# optoshield-low1.net
KiCad netlist of a schematic drawn in EAGLE
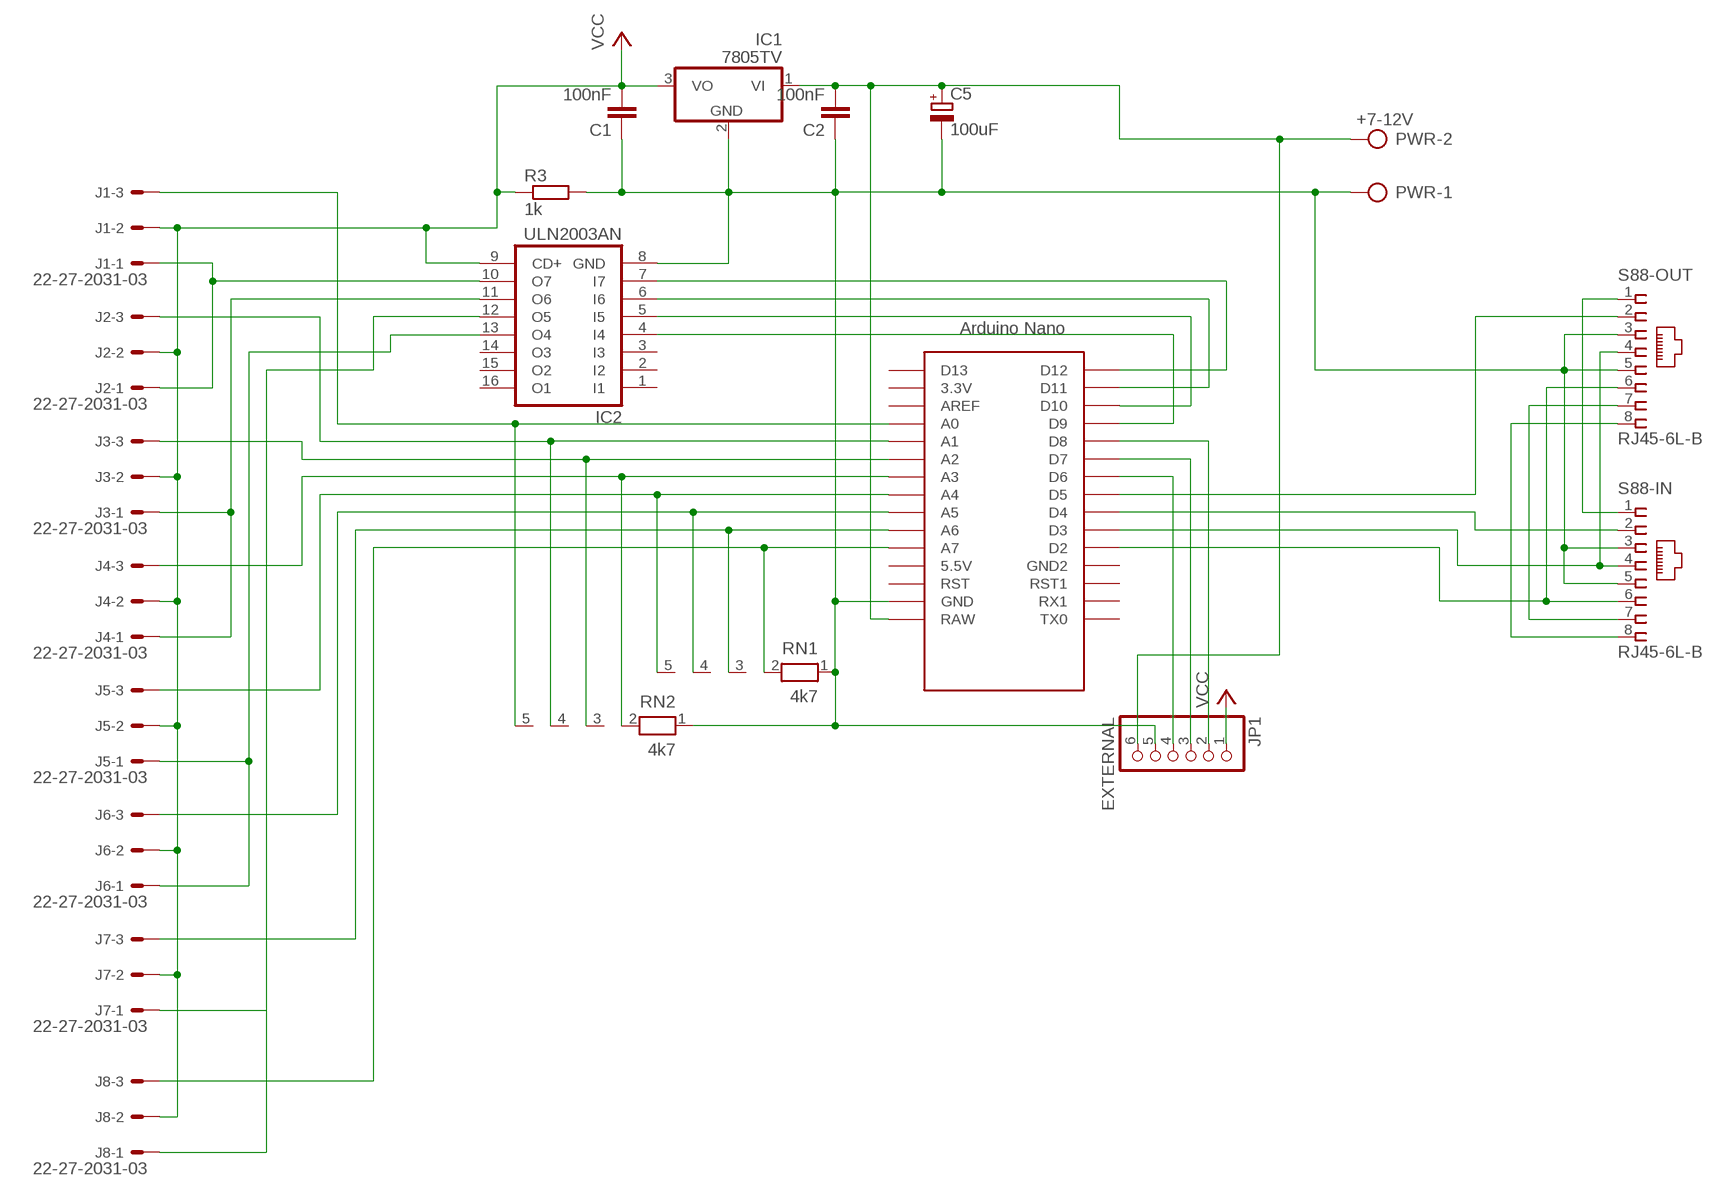
[diagram p0: schematic, sheet 1]

(export (version "E")
  (design (tool "Eeschema 10.0.6"))
  (components
    (comp (ref "C1")
      (value "100nF")
      (footprint "eagle-import:C025-025X050")
      (libsource (lib "eagle-import") (part "C-EU025-025X050"))
    )
    (comp (ref "C2")
      (value "100nF")
      (footprint "eagle-import:C025-025X050")
      (libsource (lib "eagle-import") (part "C-EU025-025X050"))
    )
    (comp (ref "C5")
      (value "100uF")
      (footprint "eagle-import:E3,5-10")
      (libsource (lib "eagle-import") (part "CPOL-EUE3.5-10"))
    )
    (comp (ref "IC1")
      (value "7805TV")
      (footprint "eagle-import:TO220V")
      (libsource (lib "eagle-import") (part "78TV05"))
    )
    (comp (ref "IC2")
      (value "ULN2003AN")
      (footprint "eagle-import:DIL16")
      (libsource (lib "eagle-import") (part "ULN2003AN"))
    )
    (comp (ref "J1")
      (value "22-27-2031-03")
      (footprint "eagle-import:6410-03")
      (libsource (lib "eagle-import") (part "22-?-0327-2031"))
    )
    (comp (ref "J2")
      (value "22-27-2031-03")
      (footprint "eagle-import:6410-03")
      (libsource (lib "eagle-import") (part "22-?-0327-2031"))
    )
    (comp (ref "J3")
      (value "22-27-2031-03")
      (footprint "eagle-import:6410-03")
      (libsource (lib "eagle-import") (part "22-?-0327-2031"))
    )
    (comp (ref "J4")
      (value "22-27-2031-03")
      (footprint "eagle-import:6410-03")
      (libsource (lib "eagle-import") (part "22-?-0327-2031"))
    )
    (comp (ref "J5")
      (value "22-27-2031-03")
      (footprint "eagle-import:6410-03")
      (libsource (lib "eagle-import") (part "22-?-0327-2031"))
    )
    (comp (ref "J6")
      (value "22-27-2031-03")
      (footprint "eagle-import:6410-03")
      (libsource (lib "eagle-import") (part "22-?-0327-2031"))
    )
    (comp (ref "J7")
      (value "22-27-2031-03")
      (footprint "eagle-import:6410-03")
      (libsource (lib "eagle-import") (part "22-?-0327-2031"))
    )
    (comp (ref "J8")
      (value "22-27-2031-03")
      (footprint "eagle-import:6410-03")
      (libsource (lib "eagle-import") (part "22-?-0327-2031"))
    )
    (comp (ref "JP1")
      (value "EXTERNAL")
      (footprint "eagle-import:1X06")
      (libsource (lib "eagle-import") (part "PINHD-1X6"))
    )
    (comp (ref "PWR")
      (value "+7-12V")
      (footprint "eagle-import:AK500_2")
      (libsource (lib "eagle-import") (part "AK500/2"))
    )
    (comp (ref "R3")
      (value "1k")
      (footprint "eagle-import:0207_10")
      (libsource (lib "eagle-import") (part "R-EU_0207/10"))
    )
    (comp (ref "RN1")
      (value "4k7")
      (footprint "eagle-import:RN-5")
      (libsource (lib "eagle-import") (part "RN04"))
    )
    (comp (ref "RN2")
      (value "4k7")
      (footprint "eagle-import:RN-5")
      (libsource (lib "eagle-import") (part "RN04"))
    )
    (comp (ref "S88-IN")
      (value "RJ45-6L-B")
      (footprint "eagle-import:RJ45-NO-SHIELD")
      (libsource (lib "eagle-import") (part "RJ45-6L-B"))
    )
    (comp (ref "S88-OUT")
      (value "RJ45-6L-B")
      (footprint "eagle-import:RJ45-NO-SHIELD")
      (libsource (lib "eagle-import") (part "RJ45-6L-B"))
    )
    (comp (ref "U$1")
      (value "NANO")
      (footprint "eagle-import:NANO")
      (libsource (lib "eagle-import") (part "NANO"))
    )
  )
  (nets
    (net (code "1") (name "Net-(IC1-GND)") (class "Default")
      (node (ref "C1") (pin "1") (pinfunction "1_1") (pintype "passive"))
      (node (ref "C2") (pin "1") (pinfunction "1_1") (pintype "passive"))
      (node (ref "C5") (pin "-") (pinfunction "-_-") (pintype "passive"))
      (node (ref "IC1") (pin "2") (pinfunction "GND_2") (pintype "passive"))
      (node (ref "IC2") (pin "8") (pinfunction "GND_8") (pintype "power_in"))
      (node (ref "JP1") (pin "5") (pinfunction "5_5") (pintype "passive"))
      (node (ref "PWR") (pin "1") (pinfunction "KL_1") (pintype "passive"))
      (node (ref "R3") (pin "2") (pinfunction "2_2") (pintype "passive"))
      (node (ref "RN1") (pin "1") (pinfunction "1_1") (pintype "passive"))
      (node (ref "RN2") (pin "1") (pinfunction "1_1") (pintype "passive"))
      (node (ref "S88-IN") (pin "3") (pinfunction "3_3") (pintype "passive"))
      (node (ref "S88-IN") (pin "5") (pinfunction "5_5") (pintype "passive"))
      (node (ref "S88-OUT") (pin "3") (pinfunction "3_3") (pintype "passive"))
      (node (ref "S88-OUT") (pin "5") (pinfunction "5_5") (pintype "passive"))
      (node (ref "U$1") (pin "GND") (pinfunction "GND_GND") (pintype "bidirectional"))
    )
    (net (code "2") (name "Net-(IC1-VI)") (class "Default")
      (node (ref "C2") (pin "2") (pinfunction "2_2") (pintype "passive"))
      (node (ref "C5") (pin "+") (pinfunction "+_+") (pintype "passive"))
      (node (ref "IC1") (pin "1") (pinfunction "VI_1") (pintype "input"))
      (node (ref "JP1") (pin "6") (pinfunction "6_6") (pintype "passive"))
      (node (ref "PWR") (pin "2") (pinfunction "KL_2") (pintype "passive"))
      (node (ref "U$1") (pin "RAW") (pinfunction "RAW_RAW") (pintype "bidirectional"))
    )
    (net (code "3") (name "Net-(IC2-I4)") (class "Default")
      (node (ref "IC2") (pin "4") (pinfunction "I4_4") (pintype "input"))
      (node (ref "U$1") (pin "D9") (pinfunction "D9_D9") (pintype "bidirectional"))
    )
    (net (code "4") (name "Net-(IC2-I5)") (class "Default")
      (node (ref "IC2") (pin "5") (pinfunction "I5_5") (pintype "input"))
      (node (ref "U$1") (pin "D10") (pinfunction "D10_D10") (pintype "bidirectional"))
    )
    (net (code "5") (name "Net-(IC2-I6)") (class "Default")
      (node (ref "IC2") (pin "6") (pinfunction "I6_6") (pintype "input"))
      (node (ref "U$1") (pin "D11") (pinfunction "D11_D11") (pintype "bidirectional"))
    )
    (net (code "6") (name "Net-(IC2-I7)") (class "Default")
      (node (ref "IC2") (pin "7") (pinfunction "I7_7") (pintype "input"))
      (node (ref "U$1") (pin "D12") (pinfunction "D12_D12") (pintype "bidirectional"))
    )
    (net (code "7") (name "Net-(IC2-O4)") (class "Default")
      (node (ref "IC2") (pin "13") (pinfunction "O4_13") (pintype "open_collector"))
      (node (ref "J5") (pin "1") (pinfunction "S_1") (pintype "passive"))
      (node (ref "J6") (pin "1") (pinfunction "S_1") (pintype "passive"))
    )
    (net (code "8") (name "Net-(IC2-O5)") (class "Default")
      (node (ref "IC2") (pin "12") (pinfunction "O5_12") (pintype "open_collector"))
      (node (ref "J7") (pin "1") (pinfunction "S_1") (pintype "passive"))
      (node (ref "J8") (pin "1") (pinfunction "S_1") (pintype "passive"))
    )
    (net (code "9") (name "Net-(IC2-O6)") (class "Default")
      (node (ref "IC2") (pin "11") (pinfunction "O6_11") (pintype "open_collector"))
      (node (ref "J3") (pin "1") (pinfunction "S_1") (pintype "passive"))
      (node (ref "J4") (pin "1") (pinfunction "S_1") (pintype "passive"))
    )
    (net (code "10") (name "Net-(IC2-O7)") (class "Default")
      (node (ref "IC2") (pin "10") (pinfunction "O7_10") (pintype "open_collector"))
      (node (ref "J1") (pin "1") (pinfunction "S_1") (pintype "passive"))
      (node (ref "J2") (pin "1") (pinfunction "S_1") (pintype "passive"))
    )
    (net (code "11") (name "Net-(J1C-S)") (class "Default")
      (node (ref "J1") (pin "3") (pinfunction "S_3") (pintype "passive"))
      (node (ref "RN2") (pin "5") (pinfunction "5_5") (pintype "passive"))
      (node (ref "U$1") (pin "A0") (pinfunction "A0_A0") (pintype "bidirectional"))
    )
    (net (code "12") (name "Net-(J2C-S)") (class "Default")
      (node (ref "J2") (pin "3") (pinfunction "S_3") (pintype "passive"))
      (node (ref "RN2") (pin "4") (pinfunction "4_4") (pintype "passive"))
      (node (ref "U$1") (pin "A1") (pinfunction "A1_A1") (pintype "bidirectional"))
    )
    (net (code "13") (name "Net-(J3C-S)") (class "Default")
      (node (ref "J3") (pin "3") (pinfunction "S_3") (pintype "passive"))
      (node (ref "RN2") (pin "3") (pinfunction "3_3") (pintype "passive"))
      (node (ref "U$1") (pin "A2") (pinfunction "A2_A2") (pintype "bidirectional"))
    )
    (net (code "14") (name "Net-(J4C-S)") (class "Default")
      (node (ref "J4") (pin "3") (pinfunction "S_3") (pintype "passive"))
      (node (ref "RN2") (pin "2") (pinfunction "2_2") (pintype "passive"))
      (node (ref "U$1") (pin "A3") (pinfunction "A3_A3") (pintype "bidirectional"))
    )
    (net (code "15") (name "Net-(J5C-S)") (class "Default")
      (node (ref "J5") (pin "3") (pinfunction "S_3") (pintype "passive"))
      (node (ref "RN1") (pin "5") (pinfunction "5_5") (pintype "passive"))
      (node (ref "U$1") (pin "A4") (pinfunction "A4_A4") (pintype "bidirectional"))
    )
    (net (code "16") (name "Net-(J6C-S)") (class "Default")
      (node (ref "J6") (pin "3") (pinfunction "S_3") (pintype "passive"))
      (node (ref "RN1") (pin "4") (pinfunction "4_4") (pintype "passive"))
      (node (ref "U$1") (pin "A5") (pinfunction "A5_A5") (pintype "bidirectional"))
    )
    (net (code "17") (name "Net-(J7C-S)") (class "Default")
      (node (ref "J7") (pin "3") (pinfunction "S_3") (pintype "passive"))
      (node (ref "RN1") (pin "3") (pinfunction "3_3") (pintype "passive"))
      (node (ref "U$1") (pin "A6") (pinfunction "A6_A6") (pintype "bidirectional"))
    )
    (net (code "18") (name "Net-(J8C-S)") (class "Default")
      (node (ref "J8") (pin "3") (pinfunction "S_3") (pintype "passive"))
      (node (ref "RN1") (pin "2") (pinfunction "2_2") (pintype "passive"))
      (node (ref "U$1") (pin "A7") (pinfunction "A7_A7") (pintype "bidirectional"))
    )
    (net (code "19") (name "Net-(JP1-Pad2)") (class "Default")
      (node (ref "JP1") (pin "2") (pinfunction "2_2") (pintype "passive"))
      (node (ref "U$1") (pin "D8") (pinfunction "D8_D8") (pintype "bidirectional"))
    )
    (net (code "20") (name "Net-(JP1-Pad3)") (class "Default")
      (node (ref "JP1") (pin "3") (pinfunction "3_3") (pintype "passive"))
      (node (ref "U$1") (pin "D7") (pinfunction "D7_D7") (pintype "bidirectional"))
    )
    (net (code "21") (name "Net-(JP1-Pad4)") (class "Default")
      (node (ref "JP1") (pin "4") (pinfunction "4_4") (pintype "passive"))
      (node (ref "U$1") (pin "D6") (pinfunction "D6_D6") (pintype "bidirectional"))
    )
    (net (code "22") (name "Net-(S88-IN-Pad1)") (class "Default")
      (node (ref "S88-IN") (pin "1") (pinfunction "1_1") (pintype "passive"))
      (node (ref "S88-OUT") (pin "1") (pinfunction "1_1") (pintype "passive"))
    )
    (net (code "23") (name "Net-(S88-IN-Pad2)") (class "Default")
      (node (ref "S88-IN") (pin "2") (pinfunction "2_2") (pintype "passive"))
      (node (ref "U$1") (pin "D4") (pinfunction "D4_D4") (pintype "bidirectional"))
    )
    (net (code "24") (name "Net-(S88-IN-Pad4)") (class "Default")
      (node (ref "S88-IN") (pin "4") (pinfunction "4_4") (pintype "passive"))
      (node (ref "S88-OUT") (pin "4") (pinfunction "4_4") (pintype "passive"))
      (node (ref "U$1") (pin "D3") (pinfunction "D3_D3") (pintype "bidirectional"))
    )
    (net (code "25") (name "Net-(S88-IN-Pad6)") (class "Default")
      (node (ref "S88-IN") (pin "6") (pinfunction "6_6") (pintype "passive"))
      (node (ref "S88-OUT") (pin "6") (pinfunction "6_6") (pintype "passive"))
      (node (ref "U$1") (pin "D2") (pinfunction "D2_D2") (pintype "bidirectional"))
    )
    (net (code "26") (name "Net-(S88-IN-Pad7)") (class "Default")
      (node (ref "S88-IN") (pin "7") (pinfunction "7_7") (pintype "passive"))
      (node (ref "S88-OUT") (pin "7") (pinfunction "7_7") (pintype "passive"))
    )
    (net (code "27") (name "Net-(S88-IN-Pad8)") (class "Default")
      (node (ref "S88-IN") (pin "8") (pinfunction "8_8") (pintype "passive"))
      (node (ref "S88-OUT") (pin "8") (pinfunction "8_8") (pintype "passive"))
    )
    (net (code "28") (name "Net-(S88-OUT-Pad2)") (class "Default")
      (node (ref "S88-OUT") (pin "2") (pinfunction "2_2") (pintype "passive"))
      (node (ref "U$1") (pin "D5") (pinfunction "D5_D5") (pintype "bidirectional"))
    )
    (net (code "29") (name "VCC") (class "Default")
      (node (ref "C1") (pin "2") (pinfunction "2_2") (pintype "passive"))
      (node (ref "IC1") (pin "3") (pinfunction "VO_3") (pintype "passive"))
      (node (ref "IC2") (pin "9") (pinfunction "CD+_9") (pintype "passive"))
      (node (ref "J1") (pin "2") (pinfunction "S_2") (pintype "passive"))
      (node (ref "J2") (pin "2") (pinfunction "S_2") (pintype "passive"))
      (node (ref "J3") (pin "2") (pinfunction "S_2") (pintype "passive"))
      (node (ref "J4") (pin "2") (pinfunction "S_2") (pintype "passive"))
      (node (ref "J5") (pin "2") (pinfunction "S_2") (pintype "passive"))
      (node (ref "J6") (pin "2") (pinfunction "S_2") (pintype "passive"))
      (node (ref "J7") (pin "2") (pinfunction "S_2") (pintype "passive"))
      (node (ref "J8") (pin "2") (pinfunction "S_2") (pintype "passive"))
      (node (ref "JP1") (pin "1") (pinfunction "1_1") (pintype "passive"))
      (node (ref "R3") (pin "1") (pinfunction "1_1") (pintype "passive"))
    )
    (net (code "30") (name "unconnected-(IC2-I1-Pad1)") (class "Default")
      (node (ref "IC2") (pin "1") (pinfunction "I1_1") (pintype "input"))
    )
    (net (code "31") (name "unconnected-(IC2-I2-Pad2)") (class "Default")
      (node (ref "IC2") (pin "2") (pinfunction "I2_2") (pintype "input"))
    )
    (net (code "32") (name "unconnected-(IC2-I3-Pad3)") (class "Default")
      (node (ref "IC2") (pin "3") (pinfunction "I3_3") (pintype "input"))
    )
    (net (code "33") (name "unconnected-(IC2-O1-Pad16)") (class "Default")
      (node (ref "IC2") (pin "16") (pinfunction "O1_16") (pintype "open_collector"))
    )
    (net (code "34") (name "unconnected-(IC2-O2-Pad15)") (class "Default")
      (node (ref "IC2") (pin "15") (pinfunction "O2_15") (pintype "open_collector"))
    )
    (net (code "35") (name "unconnected-(IC2-O3-Pad14)") (class "Default")
      (node (ref "IC2") (pin "14") (pinfunction "O3_14") (pintype "open_collector"))
    )
    (net (code "36") (name "unconnected-(U$1-5.5V-Pad5V)") (class "Default")
      (node (ref "U$1") (pin "5V") (pinfunction "5.5V_5V") (pintype "bidirectional"))
    )
    (net (code "37") (name "unconnected-(U$1-GND2-PadGND1)") (class "Default")
      (node (ref "U$1") (pin "GND1") (pinfunction "GND2_GND1") (pintype "bidirectional"))
    )
    (net (code "38") (name "unconnected-(U$1-Pad3.3V)") (class "Default")
      (node (ref "U$1") (pin "3.3V") (pinfunction "3.3V_3.3V") (pintype "bidirectional"))
    )
    (net (code "39") (name "unconnected-(U$1-PadAREF)") (class "Default")
      (node (ref "U$1") (pin "AREF") (pinfunction "AREF_AREF") (pintype "bidirectional"))
    )
    (net (code "40") (name "unconnected-(U$1-PadD13)") (class "Default")
      (node (ref "U$1") (pin "D13") (pinfunction "D13_D13") (pintype "bidirectional"))
    )
    (net (code "41") (name "unconnected-(U$1-PadICSP1)") (class "Default")
      (node (ref "U$1") (pin "ICSP1") (pinfunction "ICSP1_ICSP1") (pintype "bidirectional"))
    )
    (net (code "42") (name "unconnected-(U$1-PadICSP2)") (class "Default")
      (node (ref "U$1") (pin "ICSP2") (pinfunction "ICSP2_ICSP2") (pintype "bidirectional"))
    )
    (net (code "43") (name "unconnected-(U$1-PadICSP3)") (class "Default")
      (node (ref "U$1") (pin "ICSP3") (pinfunction "ICSP3_ICSP3") (pintype "bidirectional"))
    )
    (net (code "44") (name "unconnected-(U$1-PadICSP4)") (class "Default")
      (node (ref "U$1") (pin "ICSP4") (pinfunction "ICSP4_ICSP4") (pintype "bidirectional"))
    )
    (net (code "45") (name "unconnected-(U$1-PadICSP5)") (class "Default")
      (node (ref "U$1") (pin "ICSP5") (pinfunction "ICSP5_ICSP5") (pintype "bidirectional"))
    )
    (net (code "46") (name "unconnected-(U$1-PadICSP6)") (class "Default")
      (node (ref "U$1") (pin "ICSP6") (pinfunction "ICSP6_ICSP6") (pintype "bidirectional"))
    )
    (net (code "47") (name "unconnected-(U$1-PadRST)") (class "Default")
      (node (ref "U$1") (pin "RST") (pinfunction "RST_RST") (pintype "bidirectional"))
    )
    (net (code "48") (name "unconnected-(U$1-PadRST1)") (class "Default")
      (node (ref "U$1") (pin "RST1") (pinfunction "RST1_RST1") (pintype "bidirectional"))
    )
    (net (code "49") (name "unconnected-(U$1-PadRX1)") (class "Default")
      (node (ref "U$1") (pin "RX1") (pinfunction "RX1_RX1") (pintype "bidirectional"))
    )
    (net (code "50") (name "unconnected-(U$1-PadTX0)") (class "Default")
      (node (ref "U$1") (pin "TX0") (pinfunction "TX0_TX0") (pintype "bidirectional"))
    )
  )
)
